# Pinboard.net
KiCad netlist of a schematic drawn in Altium Designer
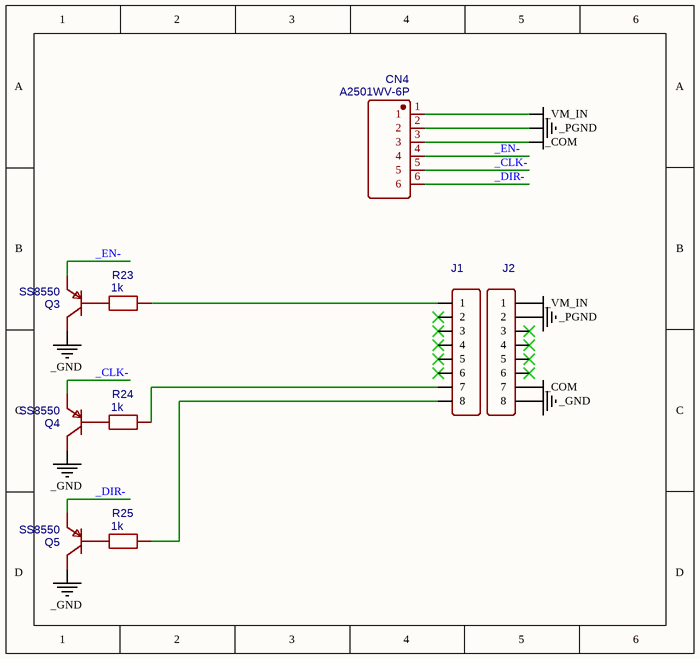
[diagram p0: Pinboard.schdoc]

(export (version "E")
  (design (tool "Eeschema 10.0.6"))
  (components
    (comp (ref "CN4")
      (value "A2501WV-6P")
      (fields (field (name "BOM_SUPPLIER PART") "C225392") (field (name "CONTRIBUTOR") "LCSC"))
      (libsource (lib "altium-import") (part "root_0_A2501WV-6P_"))
    )
    (comp (ref "J1")
      (value "HDR-M-2.54_1x8")
      (fields (field (name "BOM_SUPPLIER PART") "C190820") (field (name "CONTRIBUTOR") "LCEDA_Lib"))
      (libsource (lib "altium-import") (part "root_0_HDR-M-2.54_1x8_"))
    )
    (comp (ref "J2")
      (value "HDR-M-2.54_1x8")
      (fields (field (name "BOM_SUPPLIER PART") "C190820") (field (name "CONTRIBUTOR") "LCEDA_Lib"))
      (libsource (lib "") (part "root_0_HDR-M-2.54_1x8__1"))
    )
    (comp (ref "Q3")
      (value "SS8550")
      (fields (field (name "BOM_SUPPLIER PART") "C2762207") (field (name "CONTRIBUTOR") "LCSC"))
      (libsource (lib "altium-import") (part "root_0_SS8550_"))
    )
    (comp (ref "Q4")
      (value "SS8550")
      (fields (field (name "BOM_SUPPLIER PART") "C2762207") (field (name "CONTRIBUTOR") "LCSC"))
      (libsource (lib "altium-import") (part "root_0_SS8550_"))
    )
    (comp (ref "Q5")
      (value "SS8550")
      (fields (field (name "BOM_SUPPLIER PART") "C2762207") (field (name "CONTRIBUTOR") "LCSC"))
      (libsource (lib "altium-import") (part "root_0_SS8550_"))
    )
    (comp (ref "R23")
      (value "1k")
      (fields
        (field (name "BOM_SUPPLIER PART") "C21190")
        (field (name "BOM_MANUFACTURER PART") "0603WAF1001T5E")
        (field (name "CONTRIBUTOR") "LCEDA_Lib")
      )
      (libsource (lib "altium-import") (part "root_2_1k_"))
    )
    (comp (ref "R24")
      (value "1k")
      (fields
        (field (name "BOM_SUPPLIER PART") "C21190")
        (field (name "BOM_MANUFACTURER PART") "0603WAF1001T5E")
        (field (name "CONTRIBUTOR") "LCEDA_Lib")
      )
      (libsource (lib "altium-import") (part "root_2_1k_"))
    )
    (comp (ref "R25")
      (value "1k")
      (fields
        (field (name "BOM_SUPPLIER PART") "C21190")
        (field (name "BOM_MANUFACTURER PART") "0603WAF1001T5E")
        (field (name "CONTRIBUTOR") "LCEDA_Lib")
      )
      (libsource (lib "altium-import") (part "root_2_1k_"))
    )
  )
  (nets
    (net (code "1") (name "/_CLK-") (class "Default")
      (node (ref "CN4") (pin "5") (pinfunction "5_5") (pintype "passive"))
      (node (ref "Q4") (pin "2") (pinfunction "E_2") (pintype "passive"))
    )
    (net (code "2") (name "/_DIR-") (class "Default")
      (node (ref "CN4") (pin "6") (pinfunction "6_6") (pintype "passive"))
      (node (ref "Q5") (pin "2") (pinfunction "E_2") (pintype "passive"))
    )
    (net (code "3") (name "/_EN-") (class "Default")
      (node (ref "CN4") (pin "4") (pinfunction "4_4") (pintype "passive"))
      (node (ref "Q3") (pin "2") (pinfunction "E_2") (pintype "passive"))
    )
    (net (code "4") (name "Net-(J1-Pad1)") (class "Default")
      (node (ref "J1") (pin "1") (pinfunction "1_1") (pintype "passive"))
      (node (ref "R23") (pin "2") (pinfunction "2_2") (pintype "passive"))
    )
    (net (code "5") (name "Net-(J1-Pad7)") (class "Default")
      (node (ref "J1") (pin "7") (pinfunction "7_7") (pintype "passive"))
      (node (ref "R24") (pin "2") (pinfunction "2_2") (pintype "passive"))
    )
    (net (code "6") (name "Net-(J1-Pad8)") (class "Default")
      (node (ref "J1") (pin "8") (pinfunction "8_8") (pintype "passive"))
      (node (ref "R25") (pin "2") (pinfunction "2_2") (pintype "passive"))
    )
    (net (code "7") (name "Net-(Q3-B)") (class "Default")
      (node (ref "Q3") (pin "1") (pinfunction "B_1") (pintype "passive"))
      (node (ref "R23") (pin "1") (pinfunction "1_1") (pintype "passive"))
    )
    (net (code "8") (name "Net-(Q4-B)") (class "Default")
      (node (ref "Q4") (pin "1") (pinfunction "B_1") (pintype "passive"))
      (node (ref "R24") (pin "1") (pinfunction "1_1") (pintype "passive"))
    )
    (net (code "9") (name "Net-(Q5-B)") (class "Default")
      (node (ref "Q5") (pin "1") (pinfunction "B_1") (pintype "passive"))
      (node (ref "R25") (pin "1") (pinfunction "1_1") (pintype "passive"))
    )
    (net (code "10") (name "_COM") (class "Default")
      (node (ref "CN4") (pin "3") (pinfunction "3_3") (pintype "passive"))
      (node (ref "J2") (pin "7") (pinfunction "7_7") (pintype "passive"))
    )
    (net (code "11") (name "_GND") (class "Default")
      (node (ref "J2") (pin "8") (pinfunction "8_8") (pintype "passive"))
      (node (ref "Q3") (pin "3") (pinfunction "C_3") (pintype "passive"))
      (node (ref "Q4") (pin "3") (pinfunction "C_3") (pintype "passive"))
      (node (ref "Q5") (pin "3") (pinfunction "C_3") (pintype "passive"))
    )
    (net (code "12") (name "_PGND") (class "Default")
      (node (ref "CN4") (pin "2") (pinfunction "2_2") (pintype "passive"))
      (node (ref "J2") (pin "2") (pinfunction "2_2") (pintype "passive"))
    )
    (net (code "13") (name "_VM_IN") (class "Default")
      (node (ref "CN4") (pin "1") (pinfunction "1_1") (pintype "passive"))
      (node (ref "J2") (pin "1") (pinfunction "1_1") (pintype "passive"))
    )
    (net (code "14") (name "unconnected-(J1-Pad2)") (class "Default")
      (node (ref "J1") (pin "2") (pinfunction "2_2") (pintype "passive+no_connect"))
    )
    (net (code "15") (name "unconnected-(J1-Pad3)") (class "Default")
      (node (ref "J1") (pin "3") (pinfunction "3_3") (pintype "passive+no_connect"))
    )
    (net (code "16") (name "unconnected-(J1-Pad4)") (class "Default")
      (node (ref "J1") (pin "4") (pinfunction "4_4") (pintype "passive+no_connect"))
    )
    (net (code "17") (name "unconnected-(J1-Pad5)") (class "Default")
      (node (ref "J1") (pin "5") (pinfunction "5_5") (pintype "passive+no_connect"))
    )
    (net (code "18") (name "unconnected-(J1-Pad6)") (class "Default")
      (node (ref "J1") (pin "6") (pinfunction "6_6") (pintype "passive+no_connect"))
    )
    (net (code "19") (name "unconnected-(J2-Pad3)") (class "Default")
      (node (ref "J2") (pin "3") (pinfunction "3_3") (pintype "passive+no_connect"))
    )
    (net (code "20") (name "unconnected-(J2-Pad4)") (class "Default")
      (node (ref "J2") (pin "4") (pinfunction "4_4") (pintype "passive+no_connect"))
    )
    (net (code "21") (name "unconnected-(J2-Pad5)") (class "Default")
      (node (ref "J2") (pin "5") (pinfunction "5_5") (pintype "passive+no_connect"))
    )
    (net (code "22") (name "unconnected-(J2-Pad6)") (class "Default")
      (node (ref "J2") (pin "6") (pinfunction "6_6") (pintype "passive+no_connect"))
    )
  )
)
